# Blink_Schematic.net
KiCad netlist of a schematic drawn in EAGLE
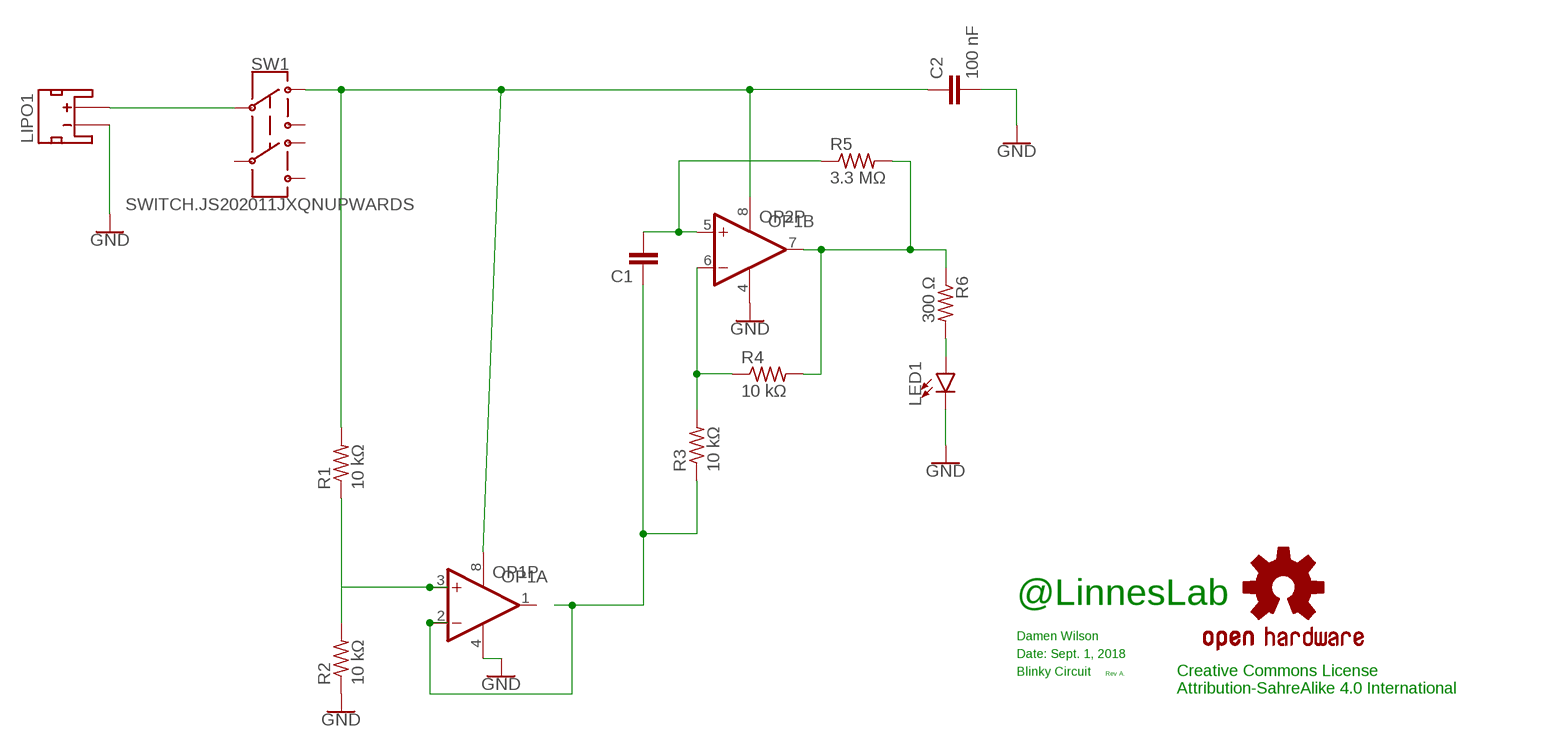
[diagram p0: schematic, sheet 1]

(export (version "E")
  (design (tool "Eeschema 10.0.6"))
  (components
    (comp (ref "C1")
      (value "C-EUC0402")
      (footprint "eagle-import:C0402")
      (libsource (lib "eagle-import") (part "C-EUC0402"))
    )
    (comp (ref "C2")
      (value "100 nF")
      (footprint "eagle-import:C0402")
      (libsource (lib "eagle-import") (part "C-EUC0402"))
    )
    (comp (ref "LED1")
      (value "LED0603")
      (footprint "eagle-import:LED-0603")
      (libsource (lib "eagle-import") (part "LED0603"))
    )
    (comp (ref "LIPO1")
      (value "JST_2MM_MALE")
      (footprint "eagle-import:JST-2-SMD")
      (libsource (lib "eagle-import") (part "JST_2MM_MALE"))
    )
    (comp (ref "LOGO1")
      (value "OSHW-LOGOS-COPPER")
      (footprint "eagle-import:OSHW-LOGO-S_COPPER")
      (libsource (lib "eagle-import") (part "OSHW-LOGOS-COPPER"))
    )
    (comp (ref "OP1")
      (value "OP-DUALRM")
      (footprint "eagle-import:MSOP08")
      (fields (field (name "MF") "ALTERA CORPORATION") (field (name "MPN") "AD8607ARMZ-REEL"))
      (libsource (lib "eagle-import") (part "OP-DUALRM"))
    )
    (comp (ref "OP2")
      (value "OP-DUALRM")
      (footprint "eagle-import:MSOP08")
      (fields (field (name "MF") "ALTERA CORPORATION") (field (name "MPN") "AD8607ARMZ-REEL"))
      (libsource (lib "eagle-import") (part "OP-DUALRM"))
    )
    (comp (ref "R1")
      (value "10 kΩ")
      (footprint "eagle-import:R0402")
      (libsource (lib "eagle-import") (part "R-US_R0402"))
    )
    (comp (ref "R2")
      (value "10 kΩ")
      (footprint "eagle-import:R0402")
      (libsource (lib "eagle-import") (part "R-US_R0402"))
    )
    (comp (ref "R3")
      (value "10 kΩ")
      (footprint "eagle-import:R0402")
      (libsource (lib "eagle-import") (part "R-US_R0402"))
    )
    (comp (ref "R4")
      (value "10 kΩ")
      (footprint "eagle-import:R0402")
      (libsource (lib "eagle-import") (part "R-US_R0402"))
    )
    (comp (ref "R5")
      (value "3.3 MΩ")
      (footprint "eagle-import:R0402")
      (libsource (lib "eagle-import") (part "R-US_R0402"))
    )
    (comp (ref "R6")
      (value "300 Ω")
      (footprint "eagle-import:R0402")
      (libsource (lib "eagle-import") (part "R-US_R0402"))
    )
    (comp (ref "SW1")
      (value "SWITCH.JS202011JXQNUPWARDS")
      (footprint "eagle-import:SWITCH.00")
      (libsource (lib "eagle-import") (part "SWITCH.JS202011JXQNUPWARDS"))
    )
  )
  (nets
    (net (code "1") (name "GND") (class "Default")
      (node (ref "C2") (pin "2") (pinfunction "2_2") (pintype "passive"))
      (node (ref "LED1") (pin "C") (pinfunction "C_C") (pintype "passive"))
      (node (ref "LIPO1") (pin "1") (pinfunction "-_1") (pintype "bidirectional"))
      (node (ref "OP1") (pin "4") (pinfunction "V-_4") (pintype "power_in"))
      (node (ref "OP2") (pin "4") (pinfunction "V-_4") (pintype "power_in"))
      (node (ref "R2") (pin "1") (pinfunction "1_1") (pintype "passive"))
    )
    (net (code "2") (name "Net-(LED1-PadA)") (class "Default")
      (node (ref "LED1") (pin "A") (pinfunction "A_A") (pintype "passive"))
      (node (ref "R6") (pin "2") (pinfunction "2_2") (pintype "passive"))
    )
    (net (code "3") (name "Net-(LIPO1-+)") (class "Default")
      (node (ref "LIPO1") (pin "2") (pinfunction "+_2") (pintype "bidirectional"))
      (node (ref "SW1") (pin "2") (pinfunction "2_2") (pintype "bidirectional"))
    )
    (net (code "4") (name "Net-(OP1A--IN)") (class "Default")
      (node (ref "C1") (pin "1") (pinfunction "1_1") (pintype "passive"))
      (node (ref "OP1") (pin "2") (pinfunction "-IN_2") (pintype "input"))
      (node (ref "R3") (pin "1") (pinfunction "1_1") (pintype "passive"))
    )
    (net (code "5") (name "Net-(OP1B-+IN)") (class "Default")
      (node (ref "C1") (pin "2") (pinfunction "2_2") (pintype "passive"))
      (node (ref "OP1") (pin "5") (pinfunction "+IN_5") (pintype "input"))
      (node (ref "R5") (pin "1") (pinfunction "1_1") (pintype "passive"))
    )
    (net (code "6") (name "Net-(OP1B--IN)") (class "Default")
      (node (ref "OP1") (pin "6") (pinfunction "-IN_6") (pintype "input"))
      (node (ref "R3") (pin "2") (pinfunction "2_2") (pintype "passive"))
      (node (ref "R4") (pin "1") (pinfunction "1_1") (pintype "passive"))
    )
    (net (code "7") (name "Net-(OP1B-OUT)") (class "Default")
      (node (ref "OP1") (pin "7") (pinfunction "OUT_7") (pintype "output"))
      (node (ref "R4") (pin "2") (pinfunction "2_2") (pintype "passive"))
      (node (ref "R5") (pin "2") (pinfunction "2_2") (pintype "passive"))
      (node (ref "R6") (pin "1") (pinfunction "1_1") (pintype "passive"))
    )
    (net (code "8") (name "Net-(OP1C-V+)") (class "Default")
      (node (ref "C2") (pin "1") (pinfunction "1_1") (pintype "passive"))
      (node (ref "OP1") (pin "8") (pinfunction "V+_8") (pintype "power_in"))
      (node (ref "OP2") (pin "8") (pinfunction "V+_8") (pintype "power_in"))
      (node (ref "R1") (pin "2") (pinfunction "2_2") (pintype "passive"))
      (node (ref "SW1") (pin "1") (pinfunction "1_1") (pintype "bidirectional"))
    )
    (net (code "9") (name "Net-(R1-Pad1)") (class "Default")
      (node (ref "R1") (pin "1") (pinfunction "1_1") (pintype "passive"))
      (node (ref "R2") (pin "2") (pinfunction "2_2") (pintype "passive"))
    )
    (net (code "10") (name "unconnected-(LIPO1-PAD1-PadNC1)") (class "Default")
      (node (ref "LIPO1") (pin "NC1") (pinfunction "PAD1_NC1") (pintype "bidirectional"))
    )
    (net (code "11") (name "unconnected-(LIPO1-PAD2-PadNC2)") (class "Default")
      (node (ref "LIPO1") (pin "NC2") (pinfunction "PAD2_NC2") (pintype "bidirectional"))
    )
    (net (code "12") (name "unconnected-(OP1A-+IN-Pad3)") (class "Default")
      (node (ref "OP1") (pin "3") (pinfunction "+IN_3") (pintype "input"))
    )
    (net (code "13") (name "unconnected-(OP1A-OUT-Pad1)") (class "Default")
      (node (ref "OP1") (pin "1") (pinfunction "OUT_1") (pintype "output"))
    )
    (net (code "14") (name "unconnected-(SW1-Pad3)") (class "Default")
      (node (ref "SW1") (pin "3") (pinfunction "3_3") (pintype "bidirectional"))
    )
    (net (code "15") (name "unconnected-(SW1-Pad5)") (class "Default")
      (node (ref "SW1") (pin "5") (pinfunction "5_5") (pintype "bidirectional"))
    )
    (net (code "16") (name "unconnected-(SW1-Pad6)") (class "Default")
      (node (ref "SW1") (pin "6") (pinfunction "6_6") (pintype "bidirectional"))
    )
    (net (code "17") (name "unconnected-(SW1-Pad7)") (class "Default")
      (node (ref "SW1") (pin "7") (pinfunction "7_7") (pintype "bidirectional"))
    )
  )
)
